# PCB-DISPLAYDOGM3.net
KiCad netlist of a schematic drawn in EAGLE
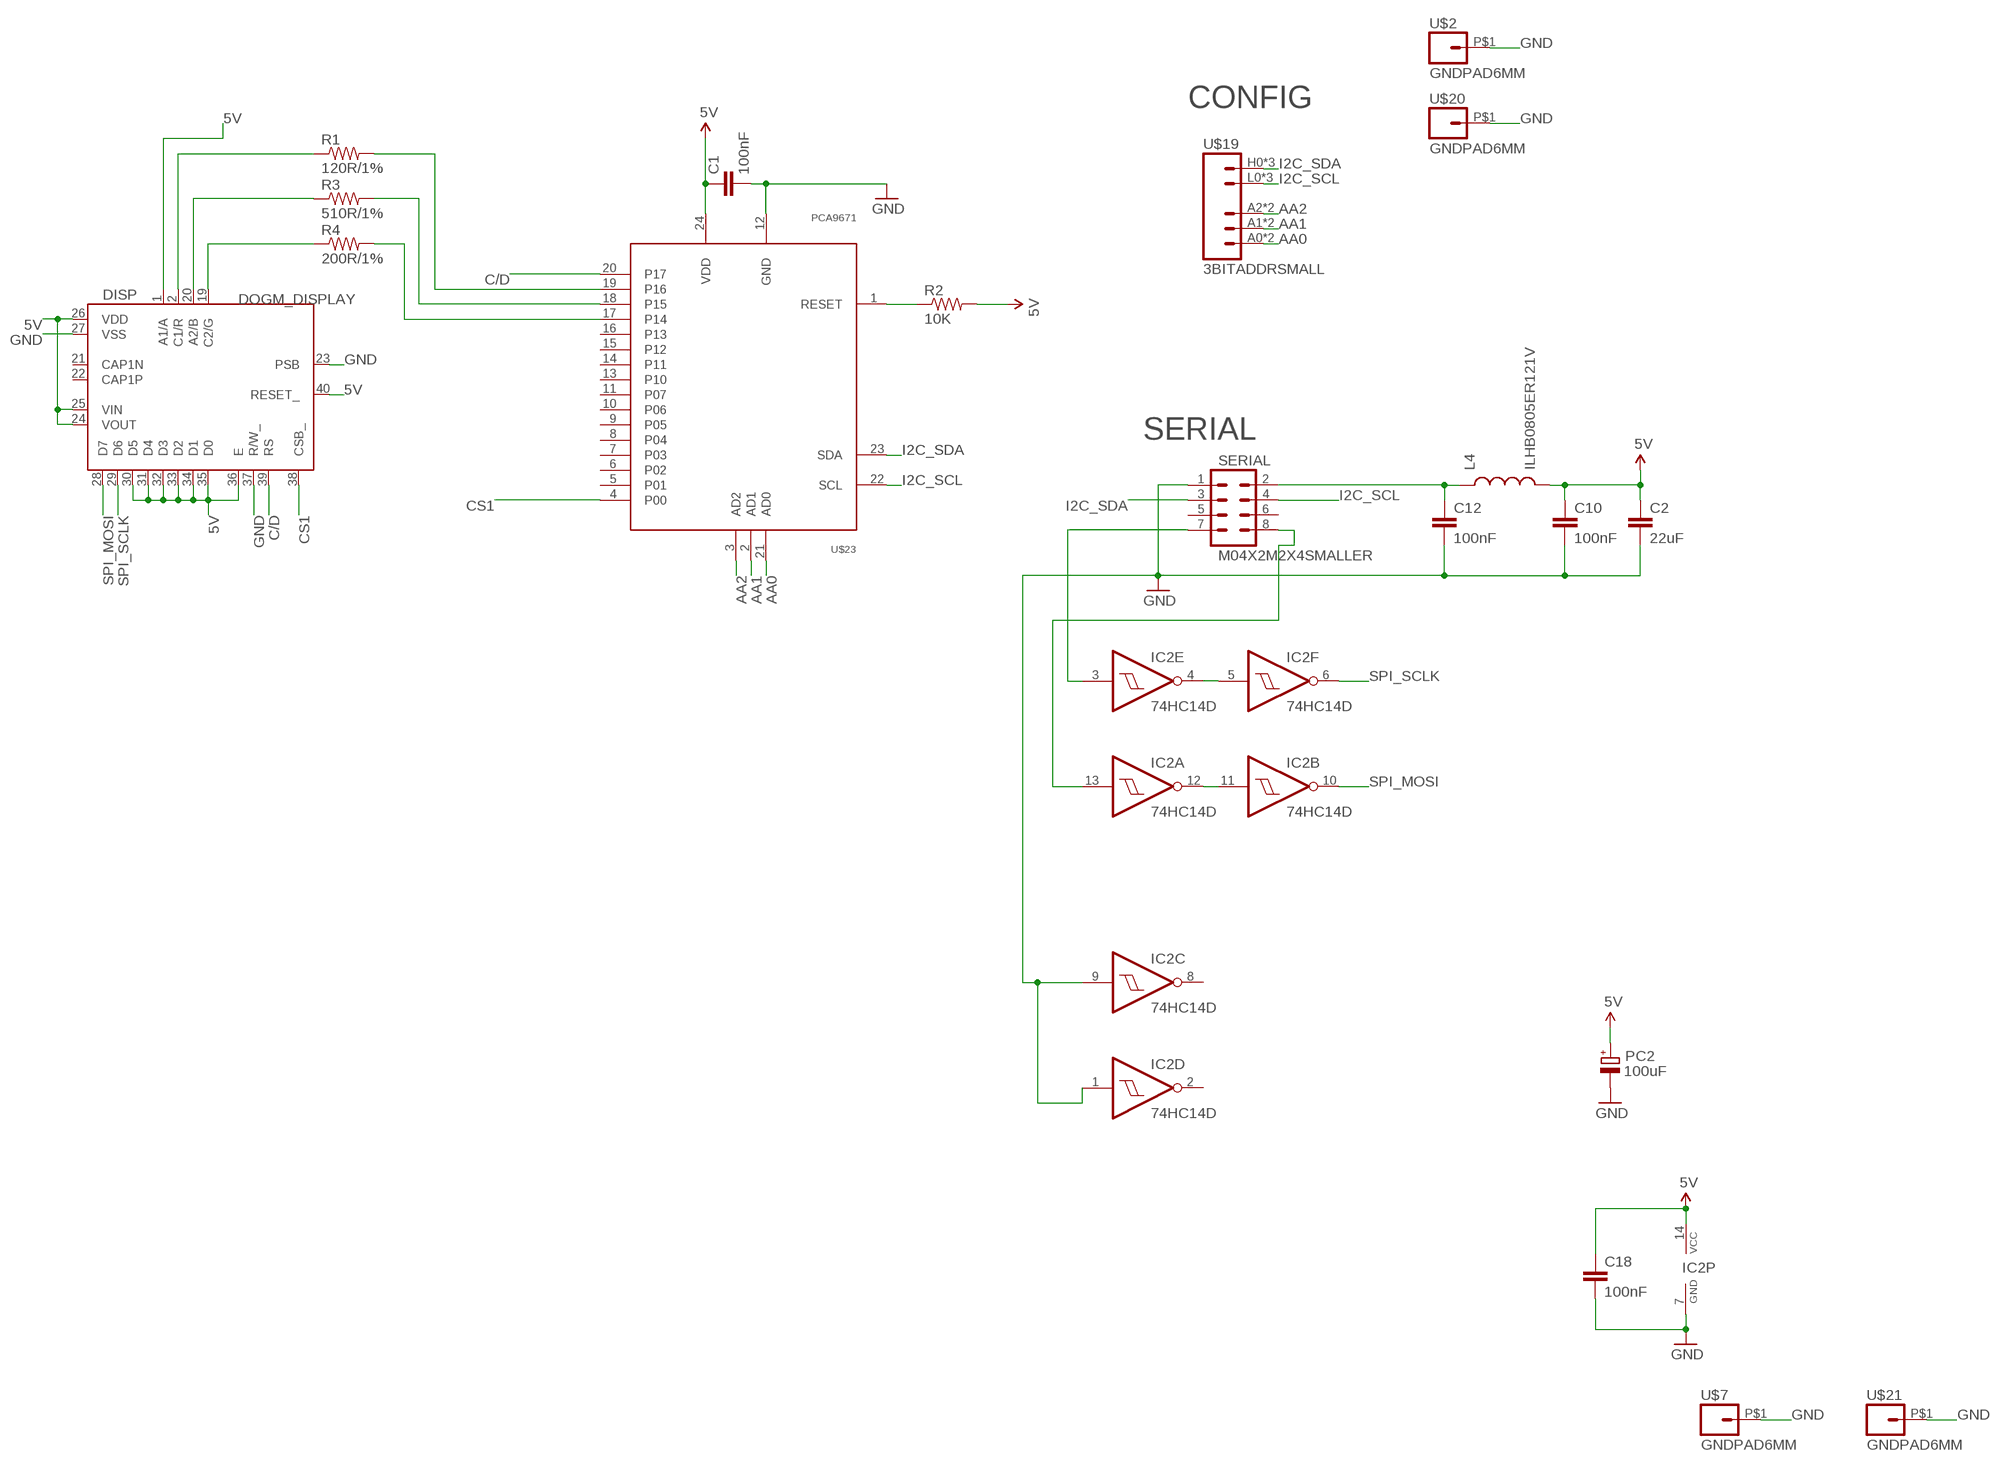
[diagram p0: schematic, sheet 1]

(export (version "E")
  (design (tool "Eeschema 10.0.6"))
  (components
    (comp (ref "C1")
      (value "100nF")
      (footprint "eagle-import:0603-CAP")
      (libsource (lib "eagle-import") (part "CAP0603-CAP"))
    )
    (comp (ref "C2")
      (value "22uF")
      (footprint "eagle-import:0805")
      (libsource (lib "eagle-import") (part "CAP0805"))
    )
    (comp (ref "C10")
      (value "100nF")
      (footprint "eagle-import:0603-CAP")
      (libsource (lib "eagle-import") (part "CAP0603-CAP"))
    )
    (comp (ref "C12")
      (value "100nF")
      (footprint "eagle-import:0603-CAP")
      (libsource (lib "eagle-import") (part "CAP0603-CAP"))
    )
    (comp (ref "C18")
      (value "100nF")
      (footprint "eagle-import:0603-CAP")
      (libsource (lib "eagle-import") (part "CAP0603-CAP"))
    )
    (comp (ref "DISP")
      (value "DOGM_DISPLAY")
      (footprint "eagle-import:DOGM")
      (libsource (lib "eagle-import") (part "DOGM_DISPLAY"))
    )
    (comp (ref "IC2")
      (value "74HC14D")
      (footprint "eagle-import:SO14")
      (libsource (lib "eagle-import") (part "7414DHC"))
    )
    (comp (ref "L4")
      (value "ILHB0805ER121V")
      (footprint "eagle-import:0805")
      (libsource (lib "eagle-import") (part "INDUCTOR0805"))
    )
    (comp (ref "PC2")
      (value "100uF")
      (footprint "eagle-import:PANASONIC_D")
      (libsource (lib "eagle-import") (part "CPOL-EUD"))
    )
    (comp (ref "R1")
      (value "120R/1%")
      (footprint "eagle-import:0603-RES")
      (libsource (lib "eagle-import") (part "RESISTOR0603-RES"))
    )
    (comp (ref "R2")
      (value "10K")
      (footprint "eagle-import:0603-RES")
      (libsource (lib "eagle-import") (part "RESISTOR0603-RES"))
    )
    (comp (ref "R3")
      (value "510R/1%")
      (footprint "eagle-import:0603-RES")
      (libsource (lib "eagle-import") (part "RESISTOR0603-RES"))
    )
    (comp (ref "R4")
      (value "200R/1%")
      (footprint "eagle-import:0603-RES")
      (libsource (lib "eagle-import") (part "RESISTOR0603-RES"))
    )
    (comp (ref "SERIAL")
      (value "M04X2M2X4SMALLER")
      (footprint "eagle-import:M2X4SMALLER")
      (libsource (lib "eagle-import") (part "M04X2M2X4SMALLER"))
    )
    (comp (ref "U$2")
      (value "GNDPAD6MM")
      (footprint "eagle-import:3.2MMPAD6MM")
      (libsource (lib "eagle-import") (part "GNDPAD6MM"))
    )
    (comp (ref "U$7")
      (value "GNDPAD6MM")
      (footprint "eagle-import:3.2MMPAD6MM")
      (libsource (lib "eagle-import") (part "GNDPAD6MM"))
    )
    (comp (ref "U$19")
      (value "3BITADDRSMALL")
      (footprint "eagle-import:3BITADDR_SMALL")
      (libsource (lib "eagle-import") (part "3BITADDRSMALL"))
    )
    (comp (ref "U$20")
      (value "GNDPAD6MM")
      (footprint "eagle-import:3.2MMPAD6MM")
      (libsource (lib "eagle-import") (part "GNDPAD6MM"))
    )
    (comp (ref "U$21")
      (value "GNDPAD6MM")
      (footprint "eagle-import:3.2MMPAD6MM")
      (libsource (lib "eagle-import") (part "GNDPAD6MM"))
    )
    (comp (ref "U$23")
      (value "PCA9671")
      (footprint "eagle-import:TSSOP24")
      (libsource (lib "eagle-import") (part "PCA9671"))
    )
  )
  (nets
    (net (code "1") (name "5V") (class "Default")
      (node (ref "C1") (pin "1") (pinfunction "1_1") (pintype "passive"))
      (node (ref "C10") (pin "1") (pinfunction "1_1") (pintype "passive"))
      (node (ref "C18") (pin "1") (pinfunction "1_1") (pintype "passive"))
      (node (ref "C2") (pin "1") (pinfunction "1_1") (pintype "passive"))
      (node (ref "DISP") (pin "1") (pinfunction "A1/A_1") (pintype "bidirectional"))
      (node (ref "DISP") (pin "24") (pinfunction "VOUT_24") (pintype "bidirectional"))
      (node (ref "DISP") (pin "25") (pinfunction "VIN_25") (pintype "bidirectional"))
      (node (ref "DISP") (pin "26") (pinfunction "VDD_26") (pintype "power_in"))
      (node (ref "DISP") (pin "30") (pinfunction "D5_30") (pintype "bidirectional"))
      (node (ref "DISP") (pin "31") (pinfunction "D4_31") (pintype "bidirectional"))
      (node (ref "DISP") (pin "32") (pinfunction "D3_32") (pintype "bidirectional"))
      (node (ref "DISP") (pin "33") (pinfunction "D2_33") (pintype "bidirectional"))
      (node (ref "DISP") (pin "34") (pinfunction "D1_34") (pintype "bidirectional"))
      (node (ref "DISP") (pin "35") (pinfunction "D0_35") (pintype "bidirectional"))
      (node (ref "DISP") (pin "36") (pinfunction "E_36") (pintype "bidirectional"))
      (node (ref "DISP") (pin "40") (pinfunction "RESET__40") (pintype "bidirectional"))
      (node (ref "IC2") (pin "14") (pinfunction "VCC_14") (pintype "power_in"))
      (node (ref "L4") (pin "2") (pinfunction "2_2") (pintype "passive"))
      (node (ref "PC2") (pin "+") (pinfunction "+_+") (pintype "passive"))
      (node (ref "R2") (pin "2") (pinfunction "2_2") (pintype "passive"))
      (node (ref "U$23") (pin "24") (pinfunction "VDD_24") (pintype "power_in"))
    )
    (net (code "2") (name "AA0") (class "Default")
      (node (ref "U$19") (pin "A0") (pinfunction "A0_A0") (pintype "passive"))
      (node (ref "U$19") (pin "AS0") (pinfunction "A0_AS0") (pintype "passive"))
      (node (ref "U$23") (pin "21") (pinfunction "AD0_21") (pintype "input"))
    )
    (net (code "3") (name "AA1") (class "Default")
      (node (ref "U$19") (pin "A1") (pinfunction "A1_A1") (pintype "passive"))
      (node (ref "U$19") (pin "AS1") (pinfunction "A1_AS1") (pintype "passive"))
      (node (ref "U$23") (pin "2") (pinfunction "AD1_2") (pintype "input"))
    )
    (net (code "4") (name "AA2") (class "Default")
      (node (ref "U$19") (pin "A2") (pinfunction "A2_A2") (pintype "passive"))
      (node (ref "U$19") (pin "AS2") (pinfunction "A2_AS2") (pintype "passive"))
      (node (ref "U$23") (pin "3") (pinfunction "AD2_3") (pintype "input"))
    )
    (net (code "5") (name "CS1") (class "Default")
      (node (ref "DISP") (pin "38") (pinfunction "CSB__38") (pintype "bidirectional"))
      (node (ref "U$23") (pin "4") (pinfunction "P00_4") (pintype "output"))
    )
    (net (code "6") (name "C{slash}D") (class "Default")
      (node (ref "DISP") (pin "39") (pinfunction "RS_39") (pintype "bidirectional"))
      (node (ref "U$23") (pin "20") (pinfunction "P17_20") (pintype "output"))
    )
    (net (code "7") (name "GND") (class "Default")
      (node (ref "C1") (pin "2") (pinfunction "2_2") (pintype "passive"))
      (node (ref "C10") (pin "2") (pinfunction "2_2") (pintype "passive"))
      (node (ref "C12") (pin "2") (pinfunction "2_2") (pintype "passive"))
      (node (ref "C18") (pin "2") (pinfunction "2_2") (pintype "passive"))
      (node (ref "C2") (pin "2") (pinfunction "2_2") (pintype "passive"))
      (node (ref "DISP") (pin "23") (pinfunction "PSB_23") (pintype "bidirectional"))
      (node (ref "DISP") (pin "27") (pinfunction "VSS_27") (pintype "power_in"))
      (node (ref "DISP") (pin "37") (pinfunction "R/W__37") (pintype "bidirectional"))
      (node (ref "IC2") (pin "1") (pinfunction "I_1") (pintype "input"))
      (node (ref "IC2") (pin "7") (pinfunction "GND_7") (pintype "power_in"))
      (node (ref "IC2") (pin "9") (pinfunction "I_9") (pintype "input"))
      (node (ref "PC2") (pin "-") (pinfunction "-_-") (pintype "passive"))
      (node (ref "SERIAL") (pin "1") (pinfunction "1_1") (pintype "passive"))
      (node (ref "U$2") (pin "P$1") (pinfunction "1_P$1") (pintype "passive"))
      (node (ref "U$20") (pin "P$1") (pinfunction "1_P$1") (pintype "passive"))
      (node (ref "U$21") (pin "P$1") (pinfunction "1_P$1") (pintype "passive"))
      (node (ref "U$23") (pin "12") (pinfunction "GND_12") (pintype "power_in"))
      (node (ref "U$7") (pin "P$1") (pinfunction "1_P$1") (pintype "passive"))
    )
    (net (code "8") (name "I2C_SCL") (class "Default")
      (node (ref "SERIAL") (pin "4") (pinfunction "4_4") (pintype "passive"))
      (node (ref "U$19") (pin "L0") (pinfunction "GND_L0") (pintype "passive"))
      (node (ref "U$19") (pin "L1") (pinfunction "GND_L1") (pintype "passive"))
      (node (ref "U$19") (pin "L2") (pinfunction "GND_L2") (pintype "passive"))
      (node (ref "U$23") (pin "22") (pinfunction "SCL_22") (pintype "input"))
    )
    (net (code "9") (name "I2C_SDA") (class "Default")
      (node (ref "SERIAL") (pin "3") (pinfunction "3_3") (pintype "passive"))
      (node (ref "U$19") (pin "H0") (pinfunction "VCC_H0") (pintype "passive"))
      (node (ref "U$19") (pin "H1") (pinfunction "VCC_H1") (pintype "passive"))
      (node (ref "U$19") (pin "H2") (pinfunction "VCC_H2") (pintype "passive"))
      (node (ref "U$23") (pin "23") (pinfunction "SDA_23") (pintype "input"))
    )
    (net (code "10") (name "Net-(C12-Pad1)") (class "Default")
      (node (ref "C12") (pin "1") (pinfunction "1_1") (pintype "passive"))
      (node (ref "L4") (pin "1") (pinfunction "1_1") (pintype "passive"))
      (node (ref "SERIAL") (pin "2") (pinfunction "2_2") (pintype "passive"))
    )
    (net (code "11") (name "Net-(DISP-A2{slash}B)") (class "Default")
      (node (ref "DISP") (pin "20") (pinfunction "A2/B_20") (pintype "bidirectional"))
      (node (ref "R3") (pin "1") (pinfunction "1_1") (pintype "passive"))
    )
    (net (code "12") (name "Net-(DISP-C1{slash}R)") (class "Default")
      (node (ref "DISP") (pin "2") (pinfunction "C1/R_2") (pintype "bidirectional"))
      (node (ref "R1") (pin "1") (pinfunction "1_1") (pintype "passive"))
    )
    (net (code "13") (name "Net-(DISP-C2{slash}G)") (class "Default")
      (node (ref "DISP") (pin "19") (pinfunction "C2/G_19") (pintype "bidirectional"))
      (node (ref "R4") (pin "1") (pinfunction "1_1") (pintype "passive"))
    )
    (net (code "14") (name "Net-(IC2A-I)") (class "Default")
      (node (ref "IC2") (pin "13") (pinfunction "I_13") (pintype "input"))
      (node (ref "SERIAL") (pin "8") (pinfunction "8_8") (pintype "passive"))
    )
    (net (code "15") (name "Net-(IC2A-O)") (class "Default")
      (node (ref "IC2") (pin "11") (pinfunction "I_11") (pintype "input"))
      (node (ref "IC2") (pin "12") (pinfunction "O_12") (pintype "output"))
    )
    (net (code "16") (name "Net-(IC2E-I)") (class "Default")
      (node (ref "IC2") (pin "3") (pinfunction "I_3") (pintype "input"))
      (node (ref "SERIAL") (pin "7") (pinfunction "7_7") (pintype "passive"))
    )
    (net (code "17") (name "Net-(IC2E-O)") (class "Default")
      (node (ref "IC2") (pin "4") (pinfunction "O_4") (pintype "output"))
      (node (ref "IC2") (pin "5") (pinfunction "I_5") (pintype "input"))
    )
    (net (code "18") (name "Net-(U$23-P14)") (class "Default")
      (node (ref "R4") (pin "2") (pinfunction "2_2") (pintype "passive"))
      (node (ref "U$23") (pin "17") (pinfunction "P14_17") (pintype "output"))
    )
    (net (code "19") (name "Net-(U$23-P15)") (class "Default")
      (node (ref "R3") (pin "2") (pinfunction "2_2") (pintype "passive"))
      (node (ref "U$23") (pin "18") (pinfunction "P15_18") (pintype "output"))
    )
    (net (code "20") (name "Net-(U$23-P16)") (class "Default")
      (node (ref "R1") (pin "2") (pinfunction "2_2") (pintype "passive"))
      (node (ref "U$23") (pin "19") (pinfunction "P16_19") (pintype "output"))
    )
    (net (code "21") (name "Net-(U$23-RESET)") (class "Default")
      (node (ref "R2") (pin "1") (pinfunction "1_1") (pintype "passive"))
      (node (ref "U$23") (pin "1") (pinfunction "RESET_1") (pintype "input"))
    )
    (net (code "22") (name "SPI_MOSI") (class "Default")
      (node (ref "DISP") (pin "28") (pinfunction "D7_28") (pintype "bidirectional"))
      (node (ref "IC2") (pin "10") (pinfunction "O_10") (pintype "output"))
    )
    (net (code "23") (name "SPI_SCLK") (class "Default")
      (node (ref "DISP") (pin "29") (pinfunction "D6_29") (pintype "bidirectional"))
      (node (ref "IC2") (pin "6") (pinfunction "O_6") (pintype "output"))
    )
    (net (code "24") (name "unconnected-(DISP-CAP1N-Pad21)") (class "Default")
      (node (ref "DISP") (pin "21") (pinfunction "CAP1N_21") (pintype "bidirectional"))
    )
    (net (code "25") (name "unconnected-(DISP-CAP1P-Pad22)") (class "Default")
      (node (ref "DISP") (pin "22") (pinfunction "CAP1P_22") (pintype "bidirectional"))
    )
    (net (code "26") (name "unconnected-(IC2C-O-Pad8)") (class "Default")
      (node (ref "IC2") (pin "8") (pinfunction "O_8") (pintype "output"))
    )
    (net (code "27") (name "unconnected-(IC2D-O-Pad2)") (class "Default")
      (node (ref "IC2") (pin "2") (pinfunction "O_2") (pintype "output"))
    )
    (net (code "28") (name "unconnected-(SERIAL-Pad5)") (class "Default")
      (node (ref "SERIAL") (pin "5") (pinfunction "5_5") (pintype "passive"))
    )
    (net (code "29") (name "unconnected-(SERIAL-Pad6)") (class "Default")
      (node (ref "SERIAL") (pin "6") (pinfunction "6_6") (pintype "passive"))
    )
    (net (code "30") (name "unconnected-(U$23-P01-Pad5)") (class "Default")
      (node (ref "U$23") (pin "5") (pinfunction "P01_5") (pintype "output"))
    )
    (net (code "31") (name "unconnected-(U$23-P02-Pad6)") (class "Default")
      (node (ref "U$23") (pin "6") (pinfunction "P02_6") (pintype "output"))
    )
    (net (code "32") (name "unconnected-(U$23-P03-Pad7)") (class "Default")
      (node (ref "U$23") (pin "7") (pinfunction "P03_7") (pintype "output"))
    )
    (net (code "33") (name "unconnected-(U$23-P04-Pad8)") (class "Default")
      (node (ref "U$23") (pin "8") (pinfunction "P04_8") (pintype "output"))
    )
    (net (code "34") (name "unconnected-(U$23-P05-Pad9)") (class "Default")
      (node (ref "U$23") (pin "9") (pinfunction "P05_9") (pintype "output"))
    )
    (net (code "35") (name "unconnected-(U$23-P06-Pad10)") (class "Default")
      (node (ref "U$23") (pin "10") (pinfunction "P06_10") (pintype "output"))
    )
    (net (code "36") (name "unconnected-(U$23-P07-Pad11)") (class "Default")
      (node (ref "U$23") (pin "11") (pinfunction "P07_11") (pintype "output"))
    )
    (net (code "37") (name "unconnected-(U$23-P10-Pad13)") (class "Default")
      (node (ref "U$23") (pin "13") (pinfunction "P10_13") (pintype "output"))
    )
    (net (code "38") (name "unconnected-(U$23-P11-Pad14)") (class "Default")
      (node (ref "U$23") (pin "14") (pinfunction "P11_14") (pintype "output"))
    )
    (net (code "39") (name "unconnected-(U$23-P12-Pad15)") (class "Default")
      (node (ref "U$23") (pin "15") (pinfunction "P12_15") (pintype "output"))
    )
    (net (code "40") (name "unconnected-(U$23-P13-Pad16)") (class "Default")
      (node (ref "U$23") (pin "16") (pinfunction "P13_16") (pintype "output"))
    )
  )
)
